# SOP-8_3_PCB.net
KiCad netlist of a schematic drawn in EAGLE
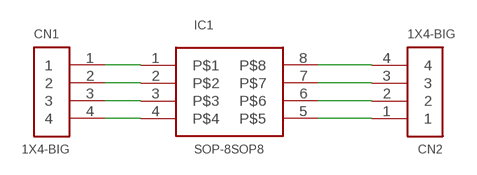
[diagram p0: schematic, sheet 1]

(export (version "E")
  (design (tool "Eeschema 10.0.6"))
  (components
    (comp (ref "CN1")
      (value "1X4-BIG")
      (footprint "eagle-import:1X04-BIG")
      (libsource (lib "eagle-import") (part "1X4-BIG"))
    )
    (comp (ref "CN2")
      (value "1X4-BIG")
      (footprint "eagle-import:1X04-BIG")
      (libsource (lib "eagle-import") (part "1X4-BIG"))
    )
    (comp (ref "IC1")
      (value "SOP-8SOP8")
      (footprint "eagle-import:SOP-8")
      (fields (field (name "MF") "Microchip") (field (name "MP") "AT24C02"))
      (libsource (lib "eagle-import") (part "SOP-8SOP8"))
    )
  )
  (nets
    (net (code "1") (name "Net-(IC1-P$1)") (class "Default")
      (node (ref "CN1") (pin "1") (pinfunction "1_1") (pintype "bidirectional"))
      (node (ref "IC1") (pin "1") (pinfunction "P$1_1") (pintype "bidirectional"))
    )
    (net (code "2") (name "Net-(IC1-P$2)") (class "Default")
      (node (ref "CN1") (pin "2") (pinfunction "2_2") (pintype "bidirectional"))
      (node (ref "IC1") (pin "2") (pinfunction "P$2_2") (pintype "bidirectional"))
    )
    (net (code "3") (name "Net-(IC1-P$3)") (class "Default")
      (node (ref "CN1") (pin "3") (pinfunction "3_3") (pintype "bidirectional"))
      (node (ref "IC1") (pin "3") (pinfunction "P$3_3") (pintype "bidirectional"))
    )
    (net (code "4") (name "Net-(IC1-P$4)") (class "Default")
      (node (ref "CN1") (pin "4") (pinfunction "4_4") (pintype "bidirectional"))
      (node (ref "IC1") (pin "4") (pinfunction "P$4_4") (pintype "bidirectional"))
    )
    (net (code "5") (name "Net-(IC1-P$5)") (class "Default")
      (node (ref "CN2") (pin "1") (pinfunction "1_1") (pintype "bidirectional"))
      (node (ref "IC1") (pin "5") (pinfunction "P$5_5") (pintype "bidirectional"))
    )
    (net (code "6") (name "Net-(IC1-P$6)") (class "Default")
      (node (ref "CN2") (pin "2") (pinfunction "2_2") (pintype "bidirectional"))
      (node (ref "IC1") (pin "6") (pinfunction "P$6_6") (pintype "bidirectional"))
    )
    (net (code "7") (name "Net-(IC1-P$7)") (class "Default")
      (node (ref "CN2") (pin "3") (pinfunction "3_3") (pintype "bidirectional"))
      (node (ref "IC1") (pin "7") (pinfunction "P$7_7") (pintype "bidirectional"))
    )
    (net (code "8") (name "Net-(IC1-P$8)") (class "Default")
      (node (ref "CN2") (pin "4") (pinfunction "4_4") (pintype "bidirectional"))
      (node (ref "IC1") (pin "8") (pinfunction "P$8_8") (pintype "bidirectional"))
    )
  )
)
